# Adafruit_BNO055.net
KiCad netlist of a schematic drawn in EAGLE
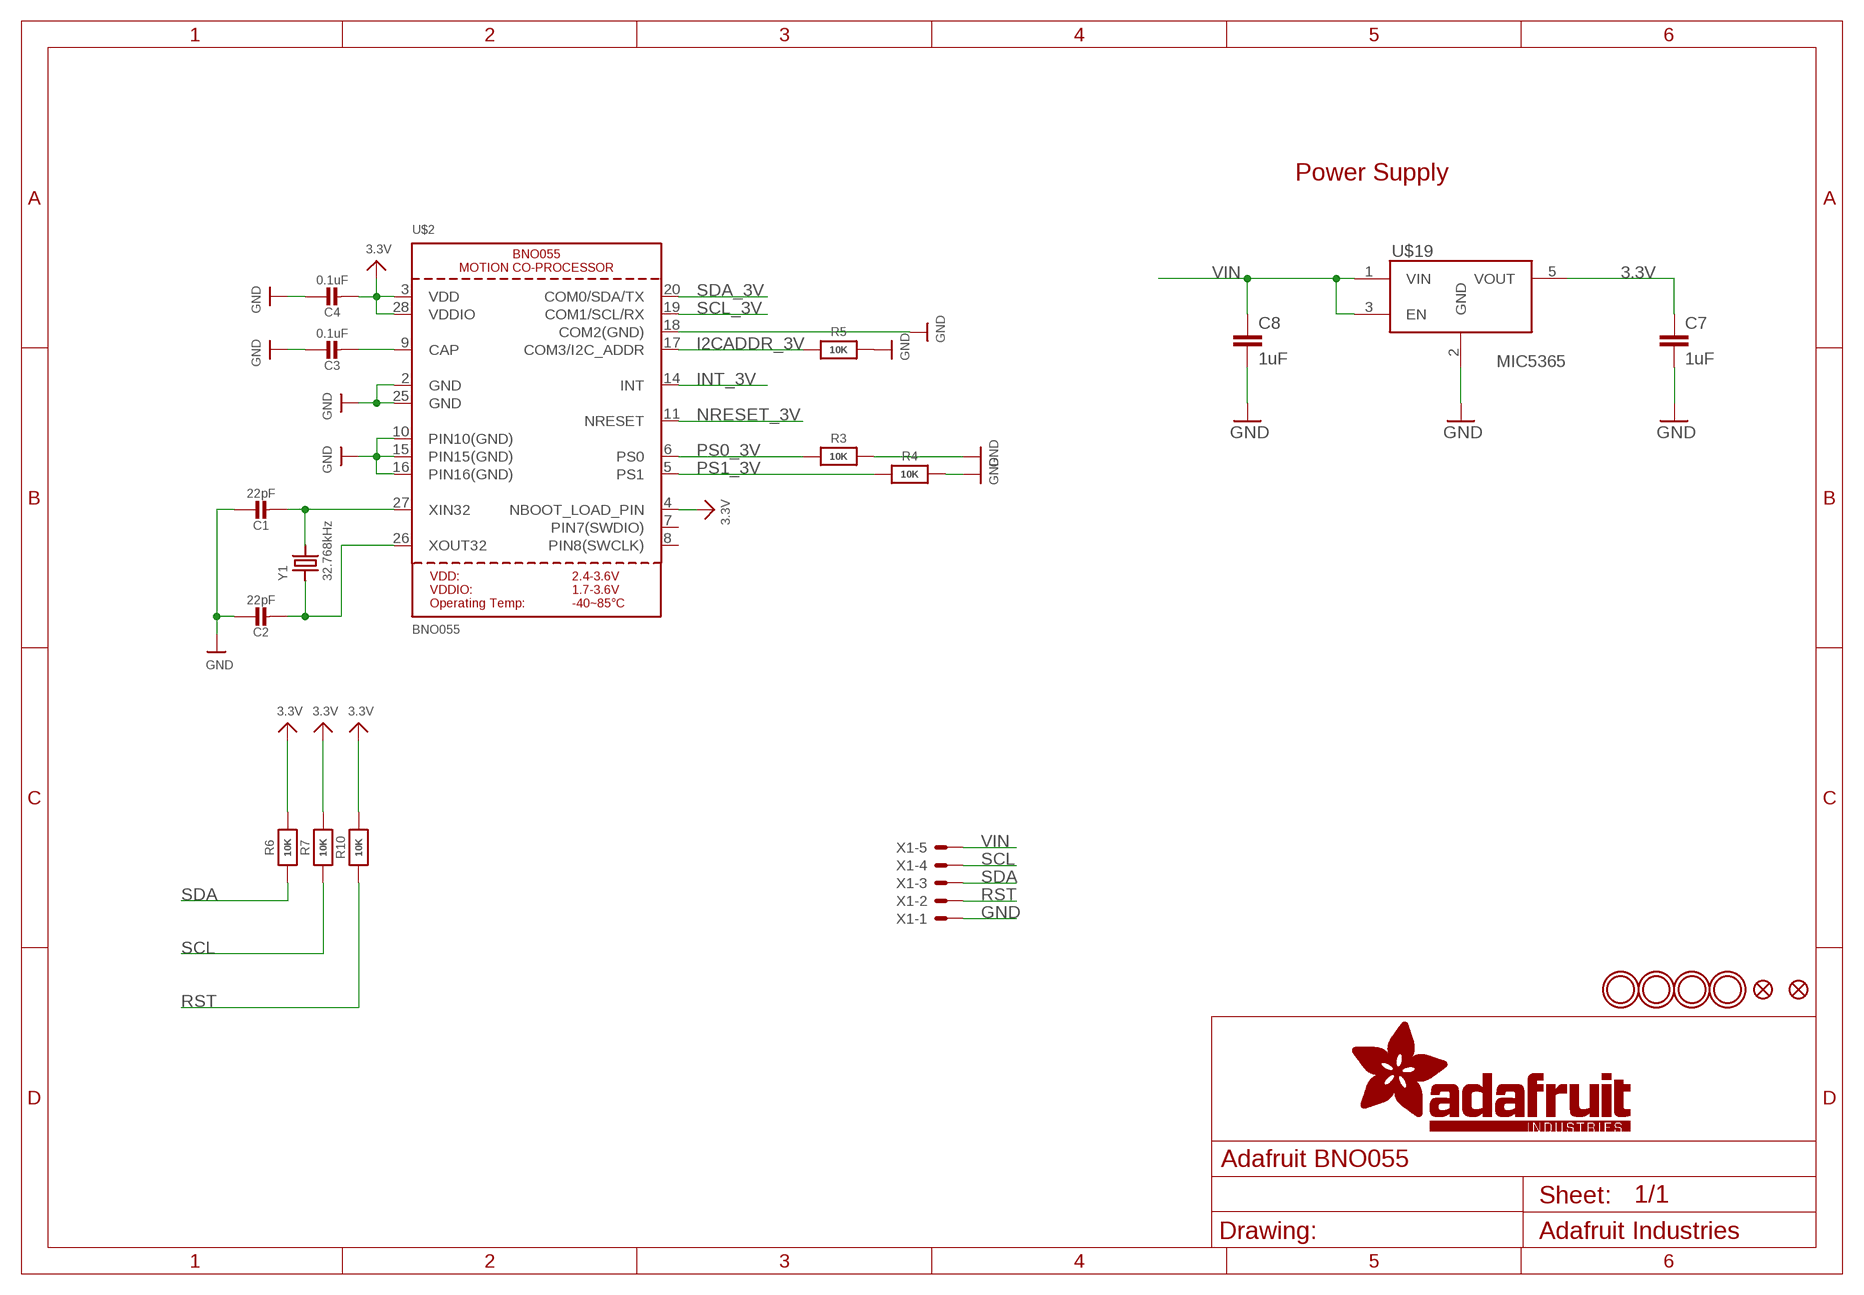
[diagram p0: schematic, sheet 1]

(export (version "E")
  (design (tool "Eeschema 10.0.6"))
  (components
    (comp (ref "C1")
      (value "22pF")
      (footprint "eagle-import:0805-NO")
      (libsource (lib "eagle-import") (part "CAP_CERAMIC0805-NOOUTLINE"))
    )
    (comp (ref "C2")
      (value "22pF")
      (footprint "eagle-import:0805-NO")
      (libsource (lib "eagle-import") (part "CAP_CERAMIC0805-NOOUTLINE"))
    )
    (comp (ref "C3")
      (value "0.1uF")
      (footprint "eagle-import:0805-NO")
      (libsource (lib "eagle-import") (part "CAP_CERAMIC0805-NOOUTLINE"))
    )
    (comp (ref "C4")
      (value "0.1uF")
      (footprint "eagle-import:0805_10MGAP")
      (libsource (lib "eagle-import") (part "CAP_CERAMIC0805_10MGAP"))
    )
    (comp (ref "C7")
      (value "1uF")
      (footprint "eagle-import:C0402")
      (libsource (lib "eagle-import") (part "C-EUC0402"))
    )
    (comp (ref "C8")
      (value "1uF")
      (footprint "eagle-import:C0402")
      (libsource (lib "eagle-import") (part "C-EUC0402"))
    )
    (comp (ref "FID1")
      (value "FIDUCIAL\"\"")
      (footprint "eagle-import:FIDUCIAL_1MM")
      (libsource (lib "eagle-import") (part "FIDUCIAL{dblquote}{dblquote}"))
    )
    (comp (ref "FID2")
      (value "FIDUCIAL\"\"")
      (footprint "eagle-import:FIDUCIAL_1MM")
      (libsource (lib "eagle-import") (part "FIDUCIAL{dblquote}{dblquote}"))
    )
    (comp (ref "R3")
      (value "10K")
      (footprint "eagle-import:0805-NO")
      (libsource (lib "eagle-import") (part "RESISTOR0805_NOOUTLINE"))
    )
    (comp (ref "R4")
      (value "10K")
      (footprint "eagle-import:0805-NO")
      (libsource (lib "eagle-import") (part "RESISTOR0805_NOOUTLINE"))
    )
    (comp (ref "R5")
      (value "10K")
      (footprint "eagle-import:0805-NO")
      (libsource (lib "eagle-import") (part "RESISTOR0805_NOOUTLINE"))
    )
    (comp (ref "R6")
      (value "10K")
      (footprint "eagle-import:0805-NO")
      (libsource (lib "eagle-import") (part "RESISTOR0805_NOOUTLINE"))
    )
    (comp (ref "R7")
      (value "10K")
      (footprint "eagle-import:0805-NO")
      (libsource (lib "eagle-import") (part "RESISTOR0805_NOOUTLINE"))
    )
    (comp (ref "R10")
      (value "10K")
      (footprint "eagle-import:0805-NO")
      (libsource (lib "eagle-import") (part "RESISTOR0805_NOOUTLINE"))
    )
    (comp (ref "U$2")
      (value "BNO055")
      (footprint "eagle-import:BNO055")
      (libsource (lib "eagle-import") (part "BNO055"))
    )
    (comp (ref "U$19")
      (value "VREG-MIC5365")
      (footprint "eagle-import:SC70-5L")
      (libsource (lib "eagle-import") (part "VREG-MIC5365"))
    )
    (comp (ref "U$29")
      (value "MOUNTINGHOLE2.5_THICK")
      (footprint "eagle-import:MOUNTINGHOLE_2.5_PLATED_THICK")
      (libsource (lib "eagle-import") (part "MOUNTINGHOLE2.5_THICK"))
    )
    (comp (ref "U$30")
      (value "MOUNTINGHOLE2.5_THICK")
      (footprint "eagle-import:MOUNTINGHOLE_2.5_PLATED_THICK")
      (libsource (lib "eagle-import") (part "MOUNTINGHOLE2.5_THICK"))
    )
    (comp (ref "U$31")
      (value "MOUNTINGHOLE2.5_THICK")
      (footprint "eagle-import:MOUNTINGHOLE_2.5_PLATED_THICK")
      (libsource (lib "eagle-import") (part "MOUNTINGHOLE2.5_THICK"))
    )
    (comp (ref "U$32")
      (value "MOUNTINGHOLE2.5_THICK")
      (footprint "eagle-import:MOUNTINGHOLE_2.5_PLATED_THICK")
      (libsource (lib "eagle-import") (part "MOUNTINGHOLE2.5_THICK"))
    )
    (comp (ref "X1")
      (value "JST-XH-05-PIN-LONG-PAD")
      (footprint "eagle-import:JST-XH-05-PACKAGE-LONG-PAD")
      (libsource (lib "eagle-import") (part "JST-XH-05-PIN-LONG-PAD"))
    )
    (comp (ref "Y1")
      (value "32.768kHz")
      (footprint "eagle-import:CRYSTAL_8X3.8")
      (libsource (lib "eagle-import") (part "CRYSTAL8.0X3.8"))
    )
  )
  (nets
    (net (code "1") (name "/I2CADDR_3V") (class "Default")
      (node (ref "R5") (pin "1") (pinfunction "1_1") (pintype "passive"))
      (node (ref "U$2") (pin "17") (pinfunction "COM3/I2C_ADDR_17") (pintype "bidirectional"))
    )
    (net (code "2") (name "/INT_3V") (class "Default")
      (node (ref "U$2") (pin "14") (pinfunction "INT_14") (pintype "output"))
    )
    (net (code "3") (name "/NRESET_3V") (class "Default")
      (node (ref "U$2") (pin "11") (pinfunction "NRESET_11") (pintype "bidirectional"))
    )
    (net (code "4") (name "/PS0_3V") (class "Default")
      (node (ref "R3") (pin "1") (pinfunction "1_1") (pintype "passive"))
      (node (ref "U$2") (pin "6") (pinfunction "PS0_6") (pintype "input"))
    )
    (net (code "5") (name "/PS1_3V") (class "Default")
      (node (ref "R4") (pin "1") (pinfunction "1_1") (pintype "passive"))
      (node (ref "U$2") (pin "5") (pinfunction "PS1_5") (pintype "input"))
    )
    (net (code "6") (name "/RST") (class "Default")
      (node (ref "R10") (pin "1") (pinfunction "1_1") (pintype "passive"))
      (node (ref "X1") (pin "2") (pinfunction "S_2") (pintype "passive"))
    )
    (net (code "7") (name "/SCL") (class "Default")
      (node (ref "R7") (pin "1") (pinfunction "1_1") (pintype "passive"))
      (node (ref "X1") (pin "4") (pinfunction "S_4") (pintype "passive"))
    )
    (net (code "8") (name "/SCL_3V") (class "Default")
      (node (ref "U$2") (pin "19") (pinfunction "COM1/SCL/RX_19") (pintype "bidirectional"))
    )
    (net (code "9") (name "/SDA") (class "Default")
      (node (ref "R6") (pin "1") (pinfunction "1_1") (pintype "passive"))
      (node (ref "X1") (pin "3") (pinfunction "S_3") (pintype "passive"))
    )
    (net (code "10") (name "/SDA_3V") (class "Default")
      (node (ref "U$2") (pin "20") (pinfunction "COM0/SDA/TX_20") (pintype "bidirectional"))
    )
    (net (code "11") (name "/VIN") (class "Default")
      (node (ref "C8") (pin "1") (pinfunction "1_1") (pintype "passive"))
      (node (ref "U$19") (pin "1") (pinfunction "VIN_1") (pintype "bidirectional"))
      (node (ref "U$19") (pin "3") (pinfunction "EN_3") (pintype "bidirectional"))
      (node (ref "X1") (pin "5") (pinfunction "S_5") (pintype "passive"))
    )
    (net (code "12") (name "3.3V") (class "Default")
      (node (ref "C4") (pin "2") (pinfunction "2_2") (pintype "passive"))
      (node (ref "C7") (pin "1") (pinfunction "1_1") (pintype "passive"))
      (node (ref "R10") (pin "2") (pinfunction "2_2") (pintype "passive"))
      (node (ref "R6") (pin "2") (pinfunction "2_2") (pintype "passive"))
      (node (ref "R7") (pin "2") (pinfunction "2_2") (pintype "passive"))
      (node (ref "U$19") (pin "5") (pinfunction "VOUT_5") (pintype "bidirectional"))
      (node (ref "U$2") (pin "28") (pinfunction "VDDIO_28") (pintype "power_in"))
      (node (ref "U$2") (pin "3") (pinfunction "VDD_3") (pintype "power_in"))
      (node (ref "U$2") (pin "4") (pinfunction "NBOOT_LOAD_PIN_4") (pintype "bidirectional"))
    )
    (net (code "13") (name "GND") (class "Default")
      (node (ref "C1") (pin "1") (pinfunction "1_1") (pintype "passive"))
      (node (ref "C2") (pin "1") (pinfunction "1_1") (pintype "passive"))
      (node (ref "C3") (pin "1") (pinfunction "1_1") (pintype "passive"))
      (node (ref "C4") (pin "1") (pinfunction "1_1") (pintype "passive"))
      (node (ref "C7") (pin "2") (pinfunction "2_2") (pintype "passive"))
      (node (ref "C8") (pin "2") (pinfunction "2_2") (pintype "passive"))
      (node (ref "R3") (pin "2") (pinfunction "2_2") (pintype "passive"))
      (node (ref "R4") (pin "2") (pinfunction "2_2") (pintype "passive"))
      (node (ref "R5") (pin "2") (pinfunction "2_2") (pintype "passive"))
      (node (ref "U$19") (pin "2") (pinfunction "GND_2") (pintype "bidirectional"))
      (node (ref "U$2") (pin "10") (pinfunction "PIN10(GND)_10") (pintype "bidirectional"))
      (node (ref "U$2") (pin "15") (pinfunction "PIN15(GND)_15") (pintype "bidirectional"))
      (node (ref "U$2") (pin "16") (pinfunction "PIN16(GND)_16") (pintype "bidirectional"))
      (node (ref "U$2") (pin "18") (pinfunction "COM2(GND)_18") (pintype "bidirectional"))
      (node (ref "U$2") (pin "2") (pinfunction "GND_2") (pintype "power_in"))
      (node (ref "U$2") (pin "25") (pinfunction "GND_25") (pintype "power_in"))
      (node (ref "X1") (pin "1") (pinfunction "S_1") (pintype "passive"))
    )
    (net (code "14") (name "Net-(U$2-CAP)") (class "Default")
      (node (ref "C3") (pin "2") (pinfunction "2_2") (pintype "passive"))
      (node (ref "U$2") (pin "9") (pinfunction "CAP_9") (pintype "passive"))
    )
    (net (code "15") (name "Net-(U$2-XIN32)") (class "Default")
      (node (ref "C1") (pin "2") (pinfunction "2_2") (pintype "passive"))
      (node (ref "U$2") (pin "27") (pinfunction "XIN32_27") (pintype "input"))
      (node (ref "Y1") (pin "P$4") (pinfunction "2_P$4") (pintype "passive"))
    )
    (net (code "16") (name "Net-(U$2-XOUT32)") (class "Default")
      (node (ref "C2") (pin "2") (pinfunction "2_2") (pintype "passive"))
      (node (ref "U$2") (pin "26") (pinfunction "XOUT32_26") (pintype "output"))
      (node (ref "Y1") (pin "P$1") (pinfunction "1_P$1") (pintype "passive"))
    )
    (net (code "17") (name "unconnected-(U$2-PIN7(SWDIO)-Pad7)") (class "Default")
      (node (ref "U$2") (pin "7") (pinfunction "PIN7(SWDIO)_7") (pintype "bidirectional"))
    )
    (net (code "18") (name "unconnected-(U$2-PIN8(SWCLK)-Pad8)") (class "Default")
      (node (ref "U$2") (pin "8") (pinfunction "PIN8(SWCLK)_8") (pintype "bidirectional"))
    )
  )
)
